# LED_board.net
KiCad netlist of a schematic drawn in EAGLE
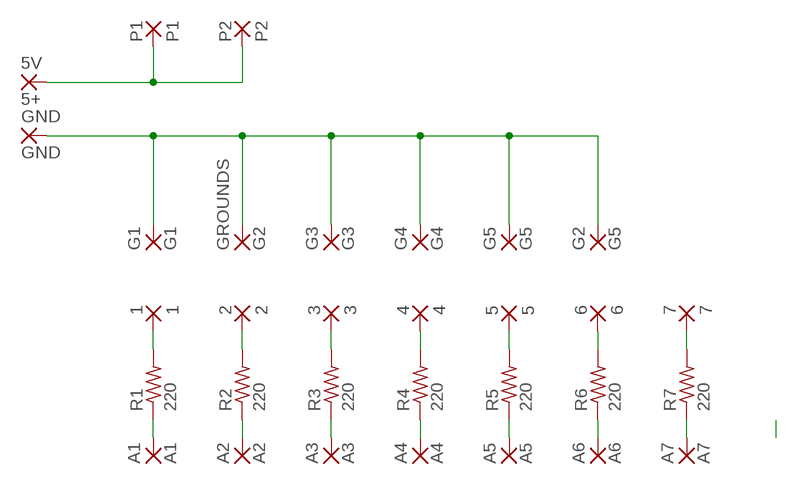
[diagram p0: schematic, sheet 1]

(export (version "E")
  (design (tool "Eeschema 10.0.6"))
  (components
    (comp (ref "1")
      (value "1")
      (footprint "eagle-import:2,15_1,0")
      (libsource (lib "eagle-import") (part "2,15/1,0"))
    )
    (comp (ref "2")
      (value "2")
      (footprint "eagle-import:2,15_1,0")
      (libsource (lib "eagle-import") (part "2,15/1,0"))
    )
    (comp (ref "3")
      (value "3")
      (footprint "eagle-import:2,15_1,0")
      (libsource (lib "eagle-import") (part "2,15/1,0"))
    )
    (comp (ref "4")
      (value "4")
      (footprint "eagle-import:2,15_1,0")
      (libsource (lib "eagle-import") (part "2,15/1,0"))
    )
    (comp (ref "5")
      (value "5")
      (footprint "eagle-import:2,15_1,0")
      (libsource (lib "eagle-import") (part "2,15/1,0"))
    )
    (comp (ref "5V")
      (value "5+")
      (footprint "eagle-import:2,54_1,1")
      (libsource (lib "eagle-import") (part "2,54/1,1"))
    )
    (comp (ref "6")
      (value "6")
      (footprint "eagle-import:2,15_1,0")
      (libsource (lib "eagle-import") (part "2,15/1,0"))
    )
    (comp (ref "7")
      (value "7")
      (footprint "eagle-import:2,15_1,0")
      (libsource (lib "eagle-import") (part "2,15/1,0"))
    )
    (comp (ref "A1")
      (value "A1")
      (footprint "eagle-import:2,15_1,0")
      (libsource (lib "eagle-import") (part "2,15/1,0"))
    )
    (comp (ref "A2")
      (value "A2")
      (footprint "eagle-import:2,15_1,0")
      (libsource (lib "eagle-import") (part "2,15/1,0"))
    )
    (comp (ref "A3")
      (value "A3")
      (footprint "eagle-import:2,15_1,0")
      (libsource (lib "eagle-import") (part "2,15/1,0"))
    )
    (comp (ref "A4")
      (value "A4")
      (footprint "eagle-import:2,15_1,0")
      (libsource (lib "eagle-import") (part "2,15/1,0"))
    )
    (comp (ref "A5")
      (value "A5")
      (footprint "eagle-import:2,15_1,0")
      (libsource (lib "eagle-import") (part "2,15/1,0"))
    )
    (comp (ref "A6")
      (value "A6")
      (footprint "eagle-import:2,15_1,0")
      (libsource (lib "eagle-import") (part "2,15/1,0"))
    )
    (comp (ref "A7")
      (value "A7")
      (footprint "eagle-import:2,15_1,0")
      (libsource (lib "eagle-import") (part "2,15/1,0"))
    )
    (comp (ref "G1")
      (value "G1")
      (footprint "eagle-import:2,15_1,0")
      (libsource (lib "eagle-import") (part "2,15/1,0"))
    )
    (comp (ref "G2")
      (value "G5")
      (footprint "eagle-import:2,15_1,0")
      (libsource (lib "eagle-import") (part "2,15/1,0"))
    )
    (comp (ref "G3")
      (value "G3")
      (footprint "eagle-import:2,15_1,0")
      (libsource (lib "eagle-import") (part "2,15/1,0"))
    )
    (comp (ref "G4")
      (value "G4")
      (footprint "eagle-import:2,15_1,0")
      (libsource (lib "eagle-import") (part "2,15/1,0"))
    )
    (comp (ref "G5")
      (value "G5")
      (footprint "eagle-import:2,15_1,0")
      (libsource (lib "eagle-import") (part "2,15/1,0"))
    )
    (comp (ref "GND")
      (value "GND")
      (footprint "eagle-import:2,54_1,1")
      (libsource (lib "eagle-import") (part "2,54/1,1"))
    )
    (comp (ref "GROUNDS")
      (value "G2")
      (footprint "eagle-import:2,15_1,0")
      (libsource (lib "eagle-import") (part "2,15/1,0"))
    )
    (comp (ref "P1")
      (value "P1")
      (footprint "eagle-import:2,15_1,0")
      (libsource (lib "eagle-import") (part "2,15/1,0"))
    )
    (comp (ref "P2")
      (value "P2")
      (footprint "eagle-import:2,15_1,0")
      (libsource (lib "eagle-import") (part "2,15/1,0"))
    )
    (comp (ref "R1")
      (value "220")
      (footprint "eagle-import:0207_10")
      (libsource (lib "eagle-import") (part "R-US_0207/10"))
    )
    (comp (ref "R2")
      (value "220")
      (footprint "eagle-import:0207_10")
      (libsource (lib "eagle-import") (part "R-US_0207/10"))
    )
    (comp (ref "R3")
      (value "220")
      (footprint "eagle-import:0207_10")
      (libsource (lib "eagle-import") (part "R-US_0207/10"))
    )
    (comp (ref "R4")
      (value "220")
      (footprint "eagle-import:0207_10")
      (libsource (lib "eagle-import") (part "R-US_0207/10"))
    )
    (comp (ref "R5")
      (value "220")
      (footprint "eagle-import:0207_10")
      (libsource (lib "eagle-import") (part "R-US_0207/10"))
    )
    (comp (ref "R6")
      (value "220")
      (footprint "eagle-import:0207_10")
      (libsource (lib "eagle-import") (part "R-US_0207/10"))
    )
    (comp (ref "R7")
      (value "220")
      (footprint "eagle-import:0207_10")
      (libsource (lib "eagle-import") (part "R-US_0207/10"))
    )
  )
  (nets
    (net (code "1") (name "Net-(1-P)") (class "Default")
      (node (ref "1") (pin "1") (pinfunction "P_1") (pintype "passive"))
      (node (ref "R1") (pin "2") (pinfunction "2_2") (pintype "passive"))
    )
    (net (code "2") (name "Net-(2-P)") (class "Default")
      (node (ref "2") (pin "1") (pinfunction "P_1") (pintype "passive"))
      (node (ref "R2") (pin "2") (pinfunction "2_2") (pintype "passive"))
    )
    (net (code "3") (name "Net-(3-P)") (class "Default")
      (node (ref "3") (pin "1") (pinfunction "P_1") (pintype "passive"))
      (node (ref "R3") (pin "2") (pinfunction "2_2") (pintype "passive"))
    )
    (net (code "4") (name "Net-(4-P)") (class "Default")
      (node (ref "4") (pin "1") (pinfunction "P_1") (pintype "passive"))
      (node (ref "R4") (pin "2") (pinfunction "2_2") (pintype "passive"))
    )
    (net (code "5") (name "Net-(5-P)") (class "Default")
      (node (ref "5") (pin "1") (pinfunction "P_1") (pintype "passive"))
      (node (ref "R5") (pin "2") (pinfunction "2_2") (pintype "passive"))
    )
    (net (code "6") (name "Net-(5V-P)") (class "Default")
      (node (ref "5V") (pin "1") (pinfunction "P_1") (pintype "passive"))
      (node (ref "P1") (pin "1") (pinfunction "P_1") (pintype "passive"))
      (node (ref "P2") (pin "1") (pinfunction "P_1") (pintype "passive"))
    )
    (net (code "7") (name "Net-(6-P)") (class "Default")
      (node (ref "6") (pin "1") (pinfunction "P_1") (pintype "passive"))
      (node (ref "R6") (pin "2") (pinfunction "2_2") (pintype "passive"))
    )
    (net (code "8") (name "Net-(7-P)") (class "Default")
      (node (ref "7") (pin "1") (pinfunction "P_1") (pintype "passive"))
      (node (ref "R7") (pin "2") (pinfunction "2_2") (pintype "passive"))
    )
    (net (code "9") (name "Net-(A1-P)") (class "Default")
      (node (ref "A1") (pin "1") (pinfunction "P_1") (pintype "passive"))
      (node (ref "R1") (pin "1") (pinfunction "1_1") (pintype "passive"))
    )
    (net (code "10") (name "Net-(A2-P)") (class "Default")
      (node (ref "A2") (pin "1") (pinfunction "P_1") (pintype "passive"))
      (node (ref "R2") (pin "1") (pinfunction "1_1") (pintype "passive"))
    )
    (net (code "11") (name "Net-(A3-P)") (class "Default")
      (node (ref "A3") (pin "1") (pinfunction "P_1") (pintype "passive"))
      (node (ref "R3") (pin "1") (pinfunction "1_1") (pintype "passive"))
    )
    (net (code "12") (name "Net-(A4-P)") (class "Default")
      (node (ref "A4") (pin "1") (pinfunction "P_1") (pintype "passive"))
      (node (ref "R4") (pin "1") (pinfunction "1_1") (pintype "passive"))
    )
    (net (code "13") (name "Net-(A5-P)") (class "Default")
      (node (ref "A5") (pin "1") (pinfunction "P_1") (pintype "passive"))
      (node (ref "R5") (pin "1") (pinfunction "1_1") (pintype "passive"))
    )
    (net (code "14") (name "Net-(A6-P)") (class "Default")
      (node (ref "A6") (pin "1") (pinfunction "P_1") (pintype "passive"))
      (node (ref "R6") (pin "1") (pinfunction "1_1") (pintype "passive"))
    )
    (net (code "15") (name "Net-(A7-P)") (class "Default")
      (node (ref "A7") (pin "1") (pinfunction "P_1") (pintype "passive"))
      (node (ref "R7") (pin "1") (pinfunction "1_1") (pintype "passive"))
    )
    (net (code "16") (name "Net-(G1-P)") (class "Default")
      (node (ref "G1") (pin "1") (pinfunction "P_1") (pintype "passive"))
      (node (ref "G2") (pin "1") (pinfunction "P_1") (pintype "passive"))
      (node (ref "G3") (pin "1") (pinfunction "P_1") (pintype "passive"))
      (node (ref "G4") (pin "1") (pinfunction "P_1") (pintype "passive"))
      (node (ref "G5") (pin "1") (pinfunction "P_1") (pintype "passive"))
      (node (ref "GND") (pin "1") (pinfunction "P_1") (pintype "passive"))
      (node (ref "GROUNDS") (pin "1") (pinfunction "P_1") (pintype "passive"))
    )
  )
)
